# MGNGSQ4_AC_Loopback.net
KiCad netlist of a schematic drawn in Altium Designer
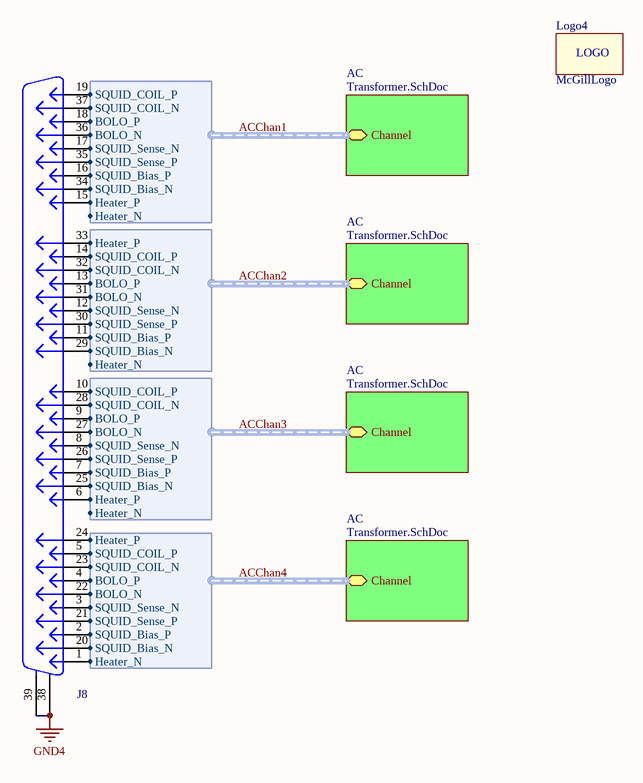
[diagram p0: MGNGSQ4_AC_Loopback.SchDoc]

(export (version "E")
  (design (tool "Eeschema 10.0.6"))
  (components
    (comp (ref "J8")
      (value "DB37M")
      (footprint "DSUB37-M")
      (fields
        (field (name "MANUFACTURER") "Norcomp")
        (field (name "MANUFACTURER PART NUMBER") "182-037-113R531")
      )
      (libsource (lib "MGNGSQ4_Dongles") (part "DB37M"))
    )
    (comp (ref "Logo4")
      (value "McGillLogo")
      (footprint "McGillLogo1")
      (description "Silkscreen Logo")
      (fields (field (name "MANUFACTURER") "McGill"))
      (libsource (lib "MGMEZZ04_Loopback") (part "Logo"))
    )
  )
  (nets
    (net (code "9") (name "GND4") (class "Default")
      (node (ref "J8") (pin "38") (pinfunction "MH1_38") (pintype "passive"))
      (node (ref "J8") (pin "39") (pinfunction "MH2_39") (pintype "passive"))
    )
    (net (code "10") (name "unconnected-(J8-Pad1)") (class "Default")
      (node (ref "J8") (pin "1") (pinfunction "1_1") (pintype "passive"))
    )
    (net (code "11") (name "unconnected-(J8-Pad2)") (class "Default")
      (node (ref "J8") (pin "2") (pinfunction "2_2") (pintype "passive"))
    )
    (net (code "12") (name "unconnected-(J8-Pad3)") (class "Default")
      (node (ref "J8") (pin "3") (pinfunction "3_3") (pintype "passive"))
    )
    (net (code "13") (name "unconnected-(J8-Pad4)") (class "Default")
      (node (ref "J8") (pin "4") (pinfunction "4_4") (pintype "passive"))
    )
    (net (code "14") (name "unconnected-(J8-Pad5)") (class "Default")
      (node (ref "J8") (pin "5") (pinfunction "5_5") (pintype "passive"))
    )
    (net (code "15") (name "unconnected-(J8-Pad6)") (class "Default")
      (node (ref "J8") (pin "6") (pinfunction "6_6") (pintype "passive"))
    )
    (net (code "16") (name "unconnected-(J8-Pad7)") (class "Default")
      (node (ref "J8") (pin "7") (pinfunction "7_7") (pintype "passive"))
    )
    (net (code "17") (name "unconnected-(J8-Pad8)") (class "Default")
      (node (ref "J8") (pin "8") (pinfunction "8_8") (pintype "passive"))
    )
    (net (code "18") (name "unconnected-(J8-Pad9)") (class "Default")
      (node (ref "J8") (pin "9") (pinfunction "9_9") (pintype "passive"))
    )
    (net (code "19") (name "unconnected-(J8-Pad10)") (class "Default")
      (node (ref "J8") (pin "10") (pinfunction "10_10") (pintype "passive"))
    )
    (net (code "20") (name "unconnected-(J8-Pad11)") (class "Default")
      (node (ref "J8") (pin "11") (pinfunction "11_11") (pintype "passive"))
    )
    (net (code "21") (name "unconnected-(J8-Pad12)") (class "Default")
      (node (ref "J8") (pin "12") (pinfunction "12_12") (pintype "passive"))
    )
    (net (code "22") (name "unconnected-(J8-Pad13)") (class "Default")
      (node (ref "J8") (pin "13") (pinfunction "13_13") (pintype "passive"))
    )
    (net (code "23") (name "unconnected-(J8-Pad14)") (class "Default")
      (node (ref "J8") (pin "14") (pinfunction "14_14") (pintype "passive"))
    )
    (net (code "24") (name "unconnected-(J8-Pad15)") (class "Default")
      (node (ref "J8") (pin "15") (pinfunction "15_15") (pintype "passive"))
    )
    (net (code "25") (name "unconnected-(J8-Pad16)") (class "Default")
      (node (ref "J8") (pin "16") (pinfunction "16_16") (pintype "passive"))
    )
    (net (code "26") (name "unconnected-(J8-Pad17)") (class "Default")
      (node (ref "J8") (pin "17") (pinfunction "17_17") (pintype "passive"))
    )
    (net (code "27") (name "unconnected-(J8-Pad18)") (class "Default")
      (node (ref "J8") (pin "18") (pinfunction "18_18") (pintype "passive"))
    )
    (net (code "28") (name "unconnected-(J8-Pad19)") (class "Default")
      (node (ref "J8") (pin "19") (pinfunction "19_19") (pintype "passive"))
    )
    (net (code "29") (name "unconnected-(J8-Pad20)") (class "Default")
      (node (ref "J8") (pin "20") (pinfunction "20_20") (pintype "passive"))
    )
    (net (code "30") (name "unconnected-(J8-Pad21)") (class "Default")
      (node (ref "J8") (pin "21") (pinfunction "21_21") (pintype "passive"))
    )
    (net (code "31") (name "unconnected-(J8-Pad22)") (class "Default")
      (node (ref "J8") (pin "22") (pinfunction "22_22") (pintype "passive"))
    )
    (net (code "32") (name "unconnected-(J8-Pad23)") (class "Default")
      (node (ref "J8") (pin "23") (pinfunction "23_23") (pintype "passive"))
    )
    (net (code "33") (name "unconnected-(J8-Pad24)") (class "Default")
      (node (ref "J8") (pin "24") (pinfunction "24_24") (pintype "passive"))
    )
    (net (code "34") (name "unconnected-(J8-Pad25)") (class "Default")
      (node (ref "J8") (pin "25") (pinfunction "25_25") (pintype "passive"))
    )
    (net (code "35") (name "unconnected-(J8-Pad26)") (class "Default")
      (node (ref "J8") (pin "26") (pinfunction "26_26") (pintype "passive"))
    )
    (net (code "36") (name "unconnected-(J8-Pad27)") (class "Default")
      (node (ref "J8") (pin "27") (pinfunction "27_27") (pintype "passive"))
    )
    (net (code "37") (name "unconnected-(J8-Pad28)") (class "Default")
      (node (ref "J8") (pin "28") (pinfunction "28_28") (pintype "passive"))
    )
    (net (code "38") (name "unconnected-(J8-Pad29)") (class "Default")
      (node (ref "J8") (pin "29") (pinfunction "29_29") (pintype "passive"))
    )
    (net (code "39") (name "unconnected-(J8-Pad30)") (class "Default")
      (node (ref "J8") (pin "30") (pinfunction "30_30") (pintype "passive"))
    )
    (net (code "40") (name "unconnected-(J8-Pad31)") (class "Default")
      (node (ref "J8") (pin "31") (pinfunction "31_31") (pintype "passive"))
    )
    (net (code "41") (name "unconnected-(J8-Pad32)") (class "Default")
      (node (ref "J8") (pin "32") (pinfunction "32_32") (pintype "passive"))
    )
    (net (code "42") (name "unconnected-(J8-Pad33)") (class "Default")
      (node (ref "J8") (pin "33") (pinfunction "33_33") (pintype "passive"))
    )
    (net (code "43") (name "unconnected-(J8-Pad34)") (class "Default")
      (node (ref "J8") (pin "34") (pinfunction "34_34") (pintype "passive"))
    )
    (net (code "44") (name "unconnected-(J8-Pad35)") (class "Default")
      (node (ref "J8") (pin "35") (pinfunction "35_35") (pintype "passive"))
    )
    (net (code "45") (name "unconnected-(J8-Pad36)") (class "Default")
      (node (ref "J8") (pin "36") (pinfunction "36_36") (pintype "passive"))
    )
    (net (code "46") (name "unconnected-(J8-Pad37)") (class "Default")
      (node (ref "J8") (pin "37") (pinfunction "37_37") (pintype "passive"))
    )
  )
)
